# DEGREE_V2.net
KiCad netlist of a schematic drawn in EAGLE
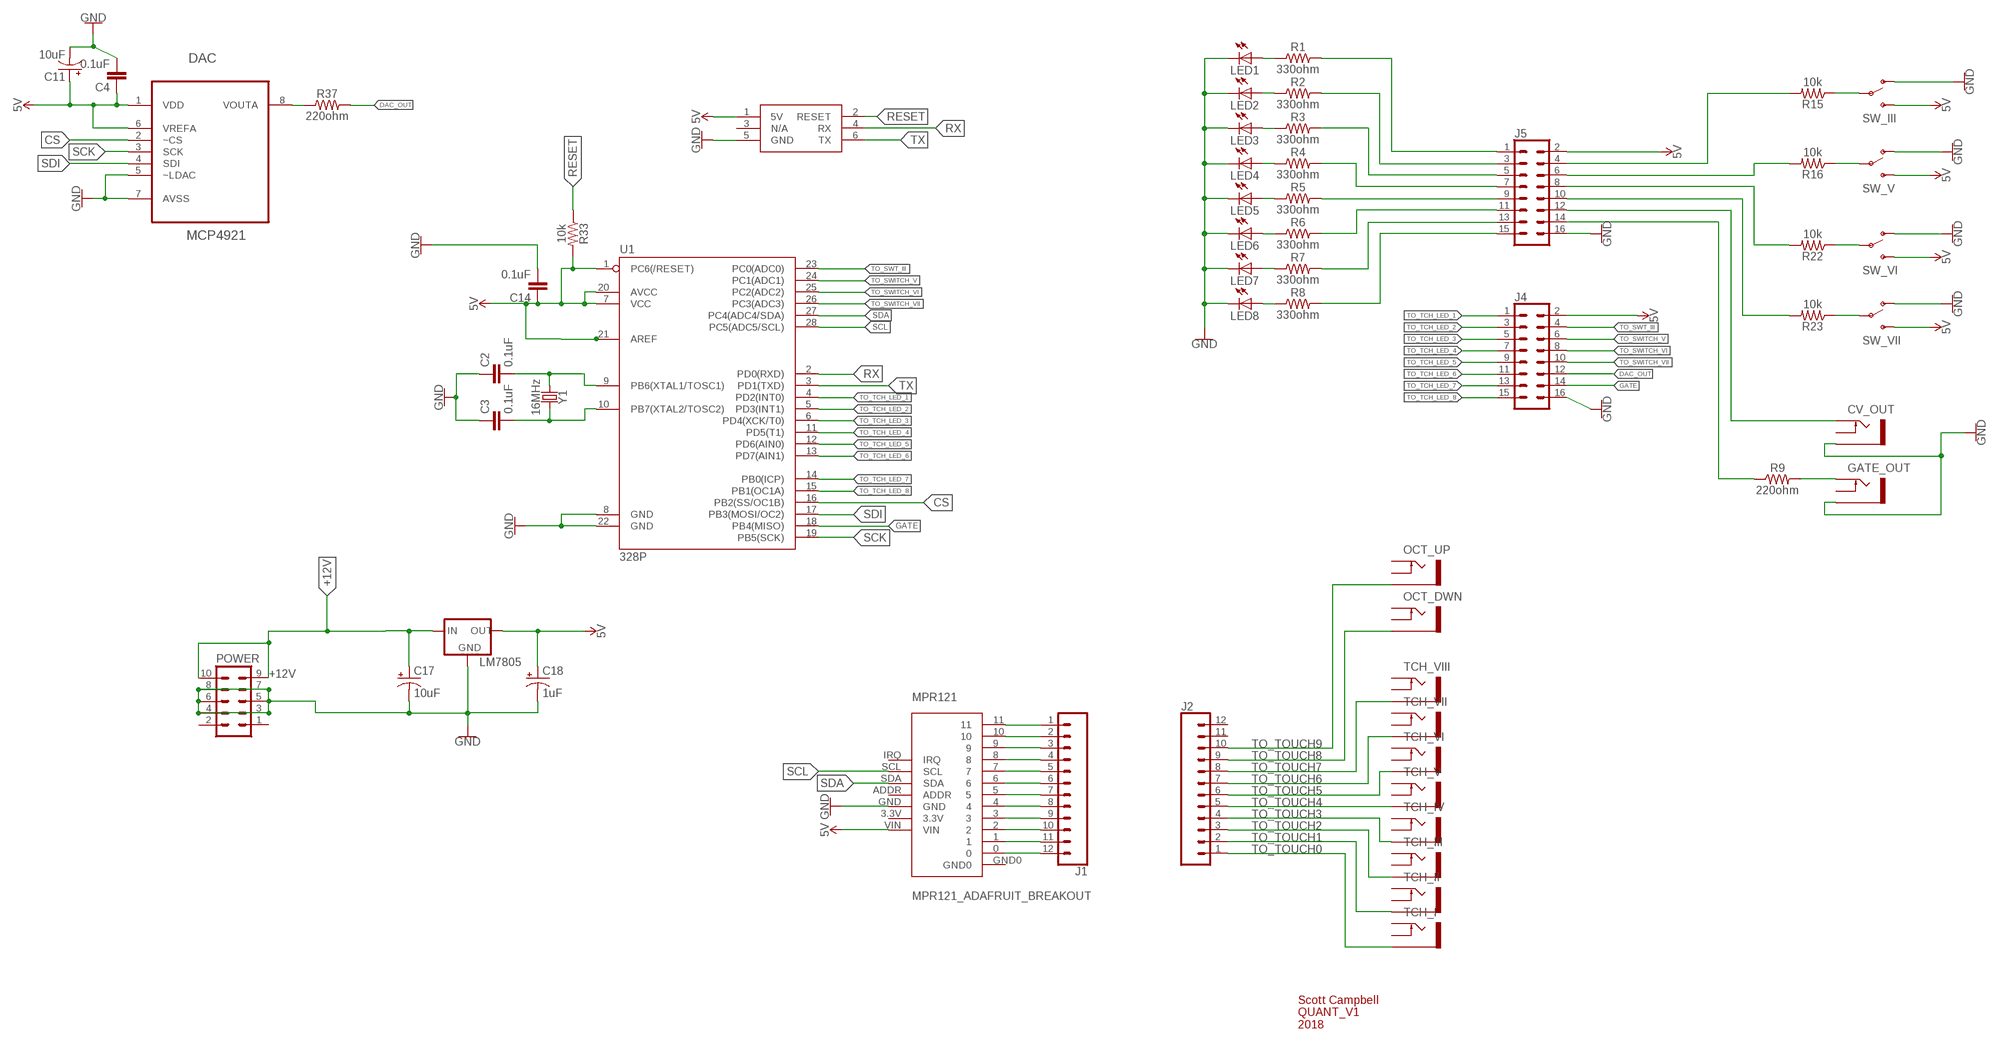
[diagram p0: schematic, sheet 1]

(export (version "E")
  (design (tool "Eeschema 10.0.6"))
  (components
    (comp (ref "C2")
      (value "0.1uF")
      (footprint "eagle-import:CAP-PTH-SMALL-KIT")
      (libsource (lib "eagle-import") (part "0.1UF-KIT-EZ-50V-20%"))
    )
    (comp (ref "C3")
      (value "0.1uF")
      (footprint "eagle-import:CAP-PTH-SMALL-KIT")
      (libsource (lib "eagle-import") (part "0.1UF-KIT-EZ-50V-20%"))
    )
    (comp (ref "C4")
      (value "0.1uF")
      (footprint "eagle-import:CAP-PTH-SMALL-KIT")
      (libsource (lib "eagle-import") (part "0.1UF-KIT-EZ-50V-20%"))
    )
    (comp (ref "C11")
      (value "10uF")
      (footprint "eagle-import:CPOL-RADIAL-2.5MM-5MM")
      (libsource (lib "eagle-import") (part "10UF-POLAR-RADIAL-2.5MM-25V-20%"))
    )
    (comp (ref "C14")
      (value "0.1uF")
      (footprint "eagle-import:CAP-PTH-SMALL-KIT")
      (libsource (lib "eagle-import") (part "0.1UF-KIT-EZ-50V-20%"))
    )
    (comp (ref "C17")
      (value "10uF")
      (footprint "eagle-import:CPOL-RADIAL-2.5MM-5MM")
      (libsource (lib "eagle-import") (part "10UF-POLAR-RADIAL-2.5MM-25V-20%"))
    )
    (comp (ref "C18")
      (value "1uF")
      (footprint "eagle-import:CPOL-RADIAL-2.5MM-5MM")
      (libsource (lib "eagle-import") (part "10UF-POLAR-RADIAL-2.5MM-25V-20%"))
    )
    (comp (ref "CV_OUT")
      (value "CV_OUT")
      (footprint "eagle-import:WQP-PJ301M-12_JACK")
      (libsource (lib "eagle-import") (part "THONKICONNNEW"))
    )
    (comp (ref "DAC")
      (value "MCP4921")
      (footprint "eagle-import:DIP08")
      (libsource (lib "eagle-import") (part "MCP4921"))
    )
    (comp (ref "GATE_OUT")
      (value "GATE_OUT")
      (footprint "eagle-import:WQP-PJ301M-12_JACK")
      (libsource (lib "eagle-import") (part "THONKICONNNEW"))
    )
    (comp (ref "J1")
      (value "CONN_12")
      (footprint "eagle-import:1X12")
      (libsource (lib "eagle-import") (part "CONN_12"))
    )
    (comp (ref "J2")
      (value "CONN_12")
      (footprint "eagle-import:1X12")
      (libsource (lib "eagle-import") (part "CONN_12"))
    )
    (comp (ref "J4")
      (value "CONN_08X2")
      (footprint "eagle-import:2X8")
      (libsource (lib "eagle-import") (part "CONN_08X2"))
    )
    (comp (ref "J5")
      (value "CONN_08X2")
      (footprint "eagle-import:2X8")
      (libsource (lib "eagle-import") (part "CONN_08X2"))
    )
    (comp (ref "LED1")
      (value "LED3MM")
      (footprint "eagle-import:LED3MM")
      (libsource (lib "eagle-import") (part "LED3MM"))
    )
    (comp (ref "LED2")
      (value "LED3MM")
      (footprint "eagle-import:LED3MM")
      (libsource (lib "eagle-import") (part "LED3MM"))
    )
    (comp (ref "LED3")
      (value "LED3MM")
      (footprint "eagle-import:LED3MM")
      (libsource (lib "eagle-import") (part "LED3MM"))
    )
    (comp (ref "LED4")
      (value "LED3MM")
      (footprint "eagle-import:LED3MM")
      (libsource (lib "eagle-import") (part "LED3MM"))
    )
    (comp (ref "LED5")
      (value "LED3MM")
      (footprint "eagle-import:LED3MM")
      (libsource (lib "eagle-import") (part "LED3MM"))
    )
    (comp (ref "LED6")
      (value "LED3MM")
      (footprint "eagle-import:LED3MM")
      (libsource (lib "eagle-import") (part "LED3MM"))
    )
    (comp (ref "LED7")
      (value "LED3MM")
      (footprint "eagle-import:LED3MM")
      (libsource (lib "eagle-import") (part "LED3MM"))
    )
    (comp (ref "LED8")
      (value "LED3MM")
      (footprint "eagle-import:LED3MM")
      (libsource (lib "eagle-import") (part "LED3MM"))
    )
    (comp (ref "LM7805")
      (value "V_REG_78XXTO-92_UNTESTED")
      (footprint "eagle-import:TO-92")
      (libsource (lib "eagle-import") (part "V_REG_78XXTO-92_UNTESTED"))
    )
    (comp (ref "MPR121")
      (value "MPR121_ADAFRUIT_BREAKOUT")
      (footprint "eagle-import:MPR121_ADAFRUIT_BREAKOUT")
      (libsource (lib "eagle-import") (part "MPR121_ADAFRUIT_BREAKOUT"))
    )
    (comp (ref "OCT_DWN")
      (value "THONKICONN-ESSY")
      (footprint "eagle-import:THONKICONN-ESSY")
      (libsource (lib "eagle-import") (part "THONKICONN-ESSY"))
    )
    (comp (ref "OCT_UP")
      (value "THONKICONN-ESSY")
      (footprint "eagle-import:THONKICONN-ESSY")
      (libsource (lib "eagle-import") (part "THONKICONN-ESSY"))
    )
    (comp (ref "POWER")
      (value "EURO_POWER_HEADERREGULAR")
      (footprint "eagle-import:EURO_POWER_HEADER")
      (libsource (lib "eagle-import") (part "EURO_POWER_HEADERREGULAR"))
    )
    (comp (ref "R1")
      (value "330ohm")
      (footprint "eagle-import:AXIAL-0.3")
      (libsource (lib "eagle-import") (part "1KOHM-HORIZ-1/4W-5%"))
    )
    (comp (ref "R2")
      (value "330ohm")
      (footprint "eagle-import:AXIAL-0.3")
      (libsource (lib "eagle-import") (part "1KOHM-HORIZ-1/4W-5%"))
    )
    (comp (ref "R3")
      (value "330ohm")
      (footprint "eagle-import:AXIAL-0.3")
      (libsource (lib "eagle-import") (part "1KOHM-HORIZ-1/4W-5%"))
    )
    (comp (ref "R4")
      (value "330ohm")
      (footprint "eagle-import:AXIAL-0.3")
      (libsource (lib "eagle-import") (part "1KOHM-HORIZ-1/4W-5%"))
    )
    (comp (ref "R5")
      (value "330ohm")
      (footprint "eagle-import:AXIAL-0.3")
      (libsource (lib "eagle-import") (part "1KOHM-HORIZ-1/4W-5%"))
    )
    (comp (ref "R6")
      (value "330ohm")
      (footprint "eagle-import:AXIAL-0.3")
      (libsource (lib "eagle-import") (part "1KOHM-HORIZ-1/4W-5%"))
    )
    (comp (ref "R7")
      (value "330ohm")
      (footprint "eagle-import:AXIAL-0.3")
      (libsource (lib "eagle-import") (part "1KOHM-HORIZ-1/4W-5%"))
    )
    (comp (ref "R8")
      (value "330ohm")
      (footprint "eagle-import:AXIAL-0.3")
      (libsource (lib "eagle-import") (part "1KOHM-HORIZ-1/4W-5%"))
    )
    (comp (ref "R9")
      (value "220ohm")
      (footprint "eagle-import:HORIZONTAL_RESISTOR")
      (libsource (lib "eagle-import") (part "RESISTOR_HORZ"))
    )
    (comp (ref "R15")
      (value "10k")
      (footprint "eagle-import:HORIZONTAL_RESISTOR")
      (libsource (lib "eagle-import") (part "RESISTOR_HORZ"))
    )
    (comp (ref "R16")
      (value "10k")
      (footprint "eagle-import:HORIZONTAL_RESISTOR")
      (libsource (lib "eagle-import") (part "RESISTOR_HORZ"))
    )
    (comp (ref "R22")
      (value "10k")
      (footprint "eagle-import:HORIZONTAL_RESISTOR")
      (libsource (lib "eagle-import") (part "RESISTOR_HORZ"))
    )
    (comp (ref "R23")
      (value "10k")
      (footprint "eagle-import:HORIZONTAL_RESISTOR")
      (libsource (lib "eagle-import") (part "RESISTOR_HORZ"))
    )
    (comp (ref "R33")
      (value "10k")
      (footprint "eagle-import:HORIZONTAL_RESISTOR")
      (libsource (lib "eagle-import") (part "RESISTOR_HORZ"))
    )
    (comp (ref "R37")
      (value "220ohm")
      (footprint "eagle-import:VERTICAL_RESISTOR")
      (libsource (lib "eagle-import") (part "RESISTOR_VERT"))
    )
    (comp (ref "SW_III")
      (value "SUBMINI_SPDT")
      (footprint "eagle-import:SUBMINI_TOGGLE")
      (libsource (lib "eagle-import") (part "SUBMINI_SPDT"))
    )
    (comp (ref "SW_V")
      (value "SUBMINI_SPDT")
      (footprint "eagle-import:SUBMINI_TOGGLE")
      (libsource (lib "eagle-import") (part "SUBMINI_SPDT"))
    )
    (comp (ref "SW_VI")
      (value "SUBMINI_SPDT")
      (footprint "eagle-import:SUBMINI_TOGGLE")
      (libsource (lib "eagle-import") (part "SUBMINI_SPDT"))
    )
    (comp (ref "SW_VII")
      (value "SUBMINI_SPDT")
      (footprint "eagle-import:SUBMINI_TOGGLE")
      (libsource (lib "eagle-import") (part "SUBMINI_SPDT"))
    )
    (comp (ref "TCH_I")
      (value "THONKICONN-ESSY")
      (footprint "eagle-import:THONKICONN-ESSY")
      (libsource (lib "eagle-import") (part "THONKICONN-ESSY"))
    )
    (comp (ref "TCH_II")
      (value "THONKICONN-ESSY")
      (footprint "eagle-import:THONKICONN-ESSY")
      (libsource (lib "eagle-import") (part "THONKICONN-ESSY"))
    )
    (comp (ref "TCH_III")
      (value "THONKICONN-ESSY")
      (footprint "eagle-import:THONKICONN-ESSY")
      (libsource (lib "eagle-import") (part "THONKICONN-ESSY"))
    )
    (comp (ref "TCH_IV")
      (value "THONKICONN-ESSY")
      (footprint "eagle-import:THONKICONN-ESSY")
      (libsource (lib "eagle-import") (part "THONKICONN-ESSY"))
    )
    (comp (ref "TCH_V")
      (value "THONKICONN-ESSY")
      (footprint "eagle-import:THONKICONN-ESSY")
      (libsource (lib "eagle-import") (part "THONKICONN-ESSY"))
    )
    (comp (ref "TCH_VI")
      (value "THONKICONN-ESSY")
      (footprint "eagle-import:THONKICONN-ESSY")
      (libsource (lib "eagle-import") (part "THONKICONN-ESSY"))
    )
    (comp (ref "TCH_VII")
      (value "THONKICONN-ESSY")
      (footprint "eagle-import:THONKICONN-ESSY")
      (libsource (lib "eagle-import") (part "THONKICONN-ESSY"))
    )
    (comp (ref "TCH_VIII")
      (value "THONKICONN-ESSY")
      (footprint "eagle-import:THONKICONN-ESSY")
      (libsource (lib "eagle-import") (part "THONKICONN-ESSY"))
    )
    (comp (ref "U$1")
      (value "ATMEGA_PROGRAMMING_PINS")
      (footprint "eagle-import:ATMEGA_PROGRAMMING_PINS")
      (libsource (lib "eagle-import") (part "ATMEGA_PROGRAMMING_PINS"))
    )
    (comp (ref "U1")
      (value "328P")
      (footprint "eagle-import:DIP28")
      (libsource (lib "eagle-import") (part "ATMEGA328P_PDIP"))
    )
    (comp (ref "Y1")
      (value "16MHz")
      (footprint "eagle-import:HC49US")
      (libsource (lib "eagle-import") (part "CRYSTAL-16MHZPTH-HC49US"))
    )
  )
  (nets
    (net (code "1") (name "+12V") (class "Default")
      (node (ref "C17") (pin "1") (pinfunction "+_1") (pintype "passive"))
      (node (ref "LM7805") (pin "3") (pinfunction "IN_3") (pintype "input"))
      (node (ref "POWER") (pin "10") (pinfunction "10_10") (pintype "passive"))
      (node (ref "POWER") (pin "9") (pinfunction "9_9") (pintype "passive"))
    )
    (net (code "2") (name "/TO_TOUCH0") (class "Default")
      (node (ref "J2") (pin "1") (pinfunction "1_1") (pintype "passive"))
      (node (ref "TCH_I") (pin "P$3_SLEEVE") (pinfunction "SLEEVE_P$3_SLEEVE") (pintype "passive"))
    )
    (net (code "3") (name "/TO_TOUCH1") (class "Default")
      (node (ref "J2") (pin "2") (pinfunction "2_2") (pintype "passive"))
      (node (ref "TCH_II") (pin "P$3_SLEEVE") (pinfunction "SLEEVE_P$3_SLEEVE") (pintype "passive"))
    )
    (net (code "4") (name "/TO_TOUCH2") (class "Default")
      (node (ref "J2") (pin "3") (pinfunction "3_3") (pintype "passive"))
      (node (ref "TCH_III") (pin "P$3_SLEEVE") (pinfunction "SLEEVE_P$3_SLEEVE") (pintype "passive"))
    )
    (net (code "5") (name "/TO_TOUCH3") (class "Default")
      (node (ref "J2") (pin "4") (pinfunction "4_4") (pintype "passive"))
      (node (ref "TCH_IV") (pin "P$3_SLEEVE") (pinfunction "SLEEVE_P$3_SLEEVE") (pintype "passive"))
    )
    (net (code "6") (name "/TO_TOUCH4") (class "Default")
      (node (ref "J2") (pin "5") (pinfunction "5_5") (pintype "passive"))
      (node (ref "TCH_V") (pin "P$3_SLEEVE") (pinfunction "SLEEVE_P$3_SLEEVE") (pintype "passive"))
    )
    (net (code "7") (name "/TO_TOUCH5") (class "Default")
      (node (ref "J2") (pin "6") (pinfunction "6_6") (pintype "passive"))
      (node (ref "TCH_VI") (pin "P$3_SLEEVE") (pinfunction "SLEEVE_P$3_SLEEVE") (pintype "passive"))
    )
    (net (code "8") (name "/TO_TOUCH6") (class "Default")
      (node (ref "J2") (pin "7") (pinfunction "7_7") (pintype "passive"))
      (node (ref "TCH_VII") (pin "P$3_SLEEVE") (pinfunction "SLEEVE_P$3_SLEEVE") (pintype "passive"))
    )
    (net (code "9") (name "/TO_TOUCH7") (class "Default")
      (node (ref "J2") (pin "8") (pinfunction "8_8") (pintype "passive"))
      (node (ref "TCH_VIII") (pin "P$3_SLEEVE") (pinfunction "SLEEVE_P$3_SLEEVE") (pintype "passive"))
    )
    (net (code "10") (name "/TO_TOUCH8") (class "Default")
      (node (ref "J2") (pin "9") (pinfunction "9_9") (pintype "passive"))
      (node (ref "OCT_DWN") (pin "P$3_SLEEVE") (pinfunction "SLEEVE_P$3_SLEEVE") (pintype "passive"))
    )
    (net (code "11") (name "/TO_TOUCH9") (class "Default")
      (node (ref "J2") (pin "10") (pinfunction "10_10") (pintype "passive"))
      (node (ref "OCT_UP") (pin "P$3_SLEEVE") (pinfunction "SLEEVE_P$3_SLEEVE") (pintype "passive"))
    )
    (net (code "12") (name "5V") (class "Default")
      (node (ref "C11") (pin "1") (pinfunction "+_1") (pintype "passive"))
      (node (ref "C14") (pin "1") (pinfunction "1_1") (pintype "passive"))
      (node (ref "C18") (pin "1") (pinfunction "+_1") (pintype "passive"))
      (node (ref "C4") (pin "1") (pinfunction "1_1") (pintype "passive"))
      (node (ref "DAC") (pin "1") (pinfunction "VDD_1") (pintype "power_in"))
      (node (ref "DAC") (pin "6") (pinfunction "VREFA_6") (pintype "input"))
      (node (ref "J4") (pin "2") (pinfunction "2_2") (pintype "passive"))
      (node (ref "J5") (pin "2") (pinfunction "2_2") (pintype "passive"))
      (node (ref "LM7805") (pin "1") (pinfunction "OUT_1") (pintype "passive"))
      (node (ref "MPR121") (pin "VIN") (pinfunction "VIN_VIN") (pintype "bidirectional"))
      (node (ref "R33") (pin "2") (pinfunction "2_2") (pintype "passive"))
      (node (ref "SW_III") (pin "3") (pinfunction "S_3") (pintype "passive"))
      (node (ref "SW_V") (pin "3") (pinfunction "S_3") (pintype "passive"))
      (node (ref "SW_VI") (pin "3") (pinfunction "S_3") (pintype "passive"))
      (node (ref "SW_VII") (pin "3") (pinfunction "S_3") (pintype "passive"))
      (node (ref "U$1") (pin "1") (pinfunction "5V_1") (pintype "bidirectional"))
      (node (ref "U1") (pin "1") (pinfunction "PC6(/RESET)_1") (pintype "bidirectional"))
      (node (ref "U1") (pin "20") (pinfunction "AVCC_20") (pintype "bidirectional"))
      (node (ref "U1") (pin "21") (pinfunction "AREF_21") (pintype "bidirectional"))
      (node (ref "U1") (pin "7") (pinfunction "VCC_7") (pintype "bidirectional"))
    )
    (net (code "13") (name "CS") (class "Default")
      (node (ref "DAC") (pin "2") (pinfunction "~{CS}_2") (pintype "input"))
      (node (ref "U1") (pin "16") (pinfunction "PB2(SS/OC1B)_16") (pintype "bidirectional"))
    )
    (net (code "14") (name "DAC_OUT") (class "Default")
      (node (ref "J4") (pin "12") (pinfunction "12_12") (pintype "passive"))
      (node (ref "R37") (pin "2") (pinfunction "2_2") (pintype "passive"))
    )
    (net (code "15") (name "GATE") (class "Default")
      (node (ref "J4") (pin "14") (pinfunction "14_14") (pintype "passive"))
      (node (ref "U1") (pin "18") (pinfunction "PB4(MISO)_18") (pintype "bidirectional"))
    )
    (net (code "16") (name "GND") (class "Default")
      (node (ref "C11") (pin "2") (pinfunction "-_2") (pintype "passive"))
      (node (ref "C14") (pin "2") (pinfunction "2_2") (pintype "passive"))
      (node (ref "C17") (pin "2") (pinfunction "-_2") (pintype "passive"))
      (node (ref "C18") (pin "2") (pinfunction "-_2") (pintype "passive"))
      (node (ref "C2") (pin "1") (pinfunction "1_1") (pintype "passive"))
      (node (ref "C3") (pin "1") (pinfunction "1_1") (pintype "passive"))
      (node (ref "C4") (pin "2") (pinfunction "2_2") (pintype "passive"))
      (node (ref "CV_OUT") (pin "P$3_SLEEVE") (pinfunction "SLEEVE_P$3_SLEEVE") (pintype "passive"))
      (node (ref "DAC") (pin "5") (pinfunction "~{LDAC}_5") (pintype "input"))
      (node (ref "DAC") (pin "7") (pinfunction "AVSS_7") (pintype "passive"))
      (node (ref "GATE_OUT") (pin "P$3_SLEEVE") (pinfunction "SLEEVE_P$3_SLEEVE") (pintype "passive"))
      (node (ref "J4") (pin "16") (pinfunction "16_16") (pintype "passive"))
      (node (ref "J5") (pin "16") (pinfunction "16_16") (pintype "passive"))
      (node (ref "LED1") (pin "K") (pinfunction "C_K") (pintype "passive"))
      (node (ref "LED2") (pin "K") (pinfunction "C_K") (pintype "passive"))
      (node (ref "LED3") (pin "K") (pinfunction "C_K") (pintype "passive"))
      (node (ref "LED4") (pin "K") (pinfunction "C_K") (pintype "passive"))
      (node (ref "LED5") (pin "K") (pinfunction "C_K") (pintype "passive"))
      (node (ref "LED6") (pin "K") (pinfunction "C_K") (pintype "passive"))
      (node (ref "LED7") (pin "K") (pinfunction "C_K") (pintype "passive"))
      (node (ref "LED8") (pin "K") (pinfunction "C_K") (pintype "passive"))
      (node (ref "LM7805") (pin "2") (pinfunction "GND_2") (pintype "input"))
      (node (ref "MPR121") (pin "GND") (pinfunction "GND_GND") (pintype "bidirectional"))
      (node (ref "POWER") (pin "3") (pinfunction "3_3") (pintype "passive"))
      (node (ref "POWER") (pin "4") (pinfunction "4_4") (pintype "passive"))
      (node (ref "POWER") (pin "5") (pinfunction "5_5") (pintype "passive"))
      (node (ref "POWER") (pin "6") (pinfunction "6_6") (pintype "passive"))
      (node (ref "POWER") (pin "7") (pinfunction "7_7") (pintype "passive"))
      (node (ref "POWER") (pin "8") (pinfunction "8_8") (pintype "passive"))
      (node (ref "SW_III") (pin "1") (pinfunction "O_1") (pintype "passive"))
      (node (ref "SW_V") (pin "1") (pinfunction "O_1") (pintype "passive"))
      (node (ref "SW_VI") (pin "1") (pinfunction "O_1") (pintype "passive"))
      (node (ref "SW_VII") (pin "1") (pinfunction "O_1") (pintype "passive"))
      (node (ref "U$1") (pin "5") (pinfunction "GND_5") (pintype "bidirectional"))
      (node (ref "U1") (pin "22") (pinfunction "GND_22") (pintype "bidirectional"))
      (node (ref "U1") (pin "8") (pinfunction "GND_8") (pintype "bidirectional"))
    )
    (net (code "17") (name "Net-(CV_OUT-TIP)") (class "Default")
      (node (ref "CV_OUT") (pin "P$1_TIP") (pinfunction "TIP_P$1_TIP") (pintype "passive"))
      (node (ref "J5") (pin "12") (pinfunction "12_12") (pintype "passive"))
    )
    (net (code "18") (name "Net-(DAC-VOUTA)") (class "Default")
      (node (ref "DAC") (pin "8") (pinfunction "VOUTA_8") (pintype "output"))
      (node (ref "R37") (pin "1") (pinfunction "1_1") (pintype "passive"))
    )
    (net (code "19") (name "Net-(GATE_OUT-TIP)") (class "Default")
      (node (ref "GATE_OUT") (pin "P$1_TIP") (pinfunction "TIP_P$1_TIP") (pintype "passive"))
      (node (ref "R9") (pin "2") (pinfunction "2_2") (pintype "passive"))
    )
    (net (code "20") (name "Net-(J1-Pad1)") (class "Default")
      (node (ref "J1") (pin "1") (pinfunction "1_1") (pintype "passive"))
      (node (ref "MPR121") (pin "11") (pinfunction "11_11") (pintype "bidirectional"))
    )
    (net (code "21") (name "Net-(J1-Pad2)") (class "Default")
      (node (ref "J1") (pin "2") (pinfunction "2_2") (pintype "passive"))
      (node (ref "MPR121") (pin "10") (pinfunction "10_10") (pintype "bidirectional"))
    )
    (net (code "22") (name "Net-(J1-Pad3)") (class "Default")
      (node (ref "J1") (pin "3") (pinfunction "3_3") (pintype "passive"))
      (node (ref "MPR121") (pin "9") (pinfunction "9_9") (pintype "bidirectional"))
    )
    (net (code "23") (name "Net-(J1-Pad4)") (class "Default")
      (node (ref "J1") (pin "4") (pinfunction "4_4") (pintype "passive"))
      (node (ref "MPR121") (pin "8") (pinfunction "8_8") (pintype "bidirectional"))
    )
    (net (code "24") (name "Net-(J1-Pad5)") (class "Default")
      (node (ref "J1") (pin "5") (pinfunction "5_5") (pintype "passive"))
      (node (ref "MPR121") (pin "7") (pinfunction "7_7") (pintype "bidirectional"))
    )
    (net (code "25") (name "Net-(J1-Pad6)") (class "Default")
      (node (ref "J1") (pin "6") (pinfunction "6_6") (pintype "passive"))
      (node (ref "MPR121") (pin "6") (pinfunction "6_6") (pintype "bidirectional"))
    )
    (net (code "26") (name "Net-(J1-Pad7)") (class "Default")
      (node (ref "J1") (pin "7") (pinfunction "7_7") (pintype "passive"))
      (node (ref "MPR121") (pin "5") (pinfunction "5_5") (pintype "bidirectional"))
    )
    (net (code "27") (name "Net-(J1-Pad8)") (class "Default")
      (node (ref "J1") (pin "8") (pinfunction "8_8") (pintype "passive"))
      (node (ref "MPR121") (pin "4") (pinfunction "4_4") (pintype "bidirectional"))
    )
    (net (code "28") (name "Net-(J1-Pad9)") (class "Default")
      (node (ref "J1") (pin "9") (pinfunction "9_9") (pintype "passive"))
      (node (ref "MPR121") (pin "3") (pinfunction "3_3") (pintype "bidirectional"))
    )
    (net (code "29") (name "Net-(J1-Pad10)") (class "Default")
      (node (ref "J1") (pin "10") (pinfunction "10_10") (pintype "passive"))
      (node (ref "MPR121") (pin "2") (pinfunction "2_2") (pintype "bidirectional"))
    )
    (net (code "30") (name "Net-(J1-Pad11)") (class "Default")
      (node (ref "J1") (pin "11") (pinfunction "11_11") (pintype "passive"))
      (node (ref "MPR121") (pin "1") (pinfunction "1_1") (pintype "bidirectional"))
    )
    (net (code "31") (name "Net-(J1-Pad12)") (class "Default")
      (node (ref "J1") (pin "12") (pinfunction "12_12") (pintype "passive"))
      (node (ref "MPR121") (pin "0") (pinfunction "0_0") (pintype "bidirectional"))
    )
    (net (code "32") (name "Net-(J5-Pad4)") (class "Default")
      (node (ref "J5") (pin "4") (pinfunction "4_4") (pintype "passive"))
      (node (ref "R15") (pin "2") (pinfunction "2_2") (pintype "passive"))
    )
    (net (code "33") (name "Net-(J5-Pad6)") (class "Default")
      (node (ref "J5") (pin "6") (pinfunction "6_6") (pintype "passive"))
      (node (ref "R16") (pin "2") (pinfunction "2_2") (pintype "passive"))
    )
    (net (code "34") (name "Net-(J5-Pad8)") (class "Default")
      (node (ref "J5") (pin "8") (pinfunction "8_8") (pintype "passive"))
      (node (ref "R22") (pin "2") (pinfunction "2_2") (pintype "passive"))
    )
    (net (code "35") (name "Net-(J5-Pad10)") (class "Default")
      (node (ref "J5") (pin "10") (pinfunction "10_10") (pintype "passive"))
      (node (ref "R23") (pin "2") (pinfunction "2_2") (pintype "passive"))
    )
    (net (code "36") (name "Net-(J5-Pad14)") (class "Default")
      (node (ref "J5") (pin "14") (pinfunction "14_14") (pintype "passive"))
      (node (ref "R9") (pin "1") (pinfunction "1_1") (pintype "passive"))
    )
    (net (code "37") (name "Net-(R1-1)") (class "Default")
      (node (ref "LED1") (pin "A") (pinfunction "A_A") (pintype "passive"))
      (node (ref "R1") (pin "P$1") (pinfunction "1_P$1") (pintype "passive"))
    )
    (net (code "38") (name "Net-(R1-2)") (class "Default")
      (node (ref "J5") (pin "1") (pinfunction "1_1") (pintype "passive"))
      (node (ref "R1") (pin "P$2") (pinfunction "2_P$2") (pintype "passive"))
    )
    (net (code "39") (name "Net-(R2-1)") (class "Default")
      (node (ref "LED2") (pin "A") (pinfunction "A_A") (pintype "passive"))
      (node (ref "R2") (pin "P$1") (pinfunction "1_P$1") (pintype "passive"))
    )
    (net (code "40") (name "Net-(R2-2)") (class "Default")
      (node (ref "J5") (pin "3") (pinfunction "3_3") (pintype "passive"))
      (node (ref "R2") (pin "P$2") (pinfunction "2_P$2") (pintype "passive"))
    )
    (net (code "41") (name "Net-(R3-1)") (class "Default")
      (node (ref "LED3") (pin "A") (pinfunction "A_A") (pintype "passive"))
      (node (ref "R3") (pin "P$1") (pinfunction "1_P$1") (pintype "passive"))
    )
    (net (code "42") (name "Net-(R3-2)") (class "Default")
      (node (ref "J5") (pin "5") (pinfunction "5_5") (pintype "passive"))
      (node (ref "R3") (pin "P$2") (pinfunction "2_P$2") (pintype "passive"))
    )
    (net (code "43") (name "Net-(R4-1)") (class "Default")
      (node (ref "LED4") (pin "A") (pinfunction "A_A") (pintype "passive"))
      (node (ref "R4") (pin "P$1") (pinfunction "1_P$1") (pintype "passive"))
    )
    (net (code "44") (name "Net-(R4-2)") (class "Default")
      (node (ref "J5") (pin "7") (pinfunction "7_7") (pintype "passive"))
      (node (ref "R4") (pin "P$2") (pinfunction "2_P$2") (pintype "passive"))
    )
    (net (code "45") (name "Net-(R5-1)") (class "Default")
      (node (ref "LED5") (pin "A") (pinfunction "A_A") (pintype "passive"))
      (node (ref "R5") (pin "P$1") (pinfunction "1_P$1") (pintype "passive"))
    )
    (net (code "46") (name "Net-(R5-2)") (class "Default")
      (node (ref "J5") (pin "9") (pinfunction "9_9") (pintype "passive"))
      (node (ref "R5") (pin "P$2") (pinfunction "2_P$2") (pintype "passive"))
    )
    (net (code "47") (name "Net-(R6-1)") (class "Default")
      (node (ref "LED6") (pin "A") (pinfunction "A_A") (pintype "passive"))
      (node (ref "R6") (pin "P$1") (pinfunction "1_P$1") (pintype "passive"))
    )
    (net (code "48") (name "Net-(R6-2)") (class "Default")
      (node (ref "J5") (pin "11") (pinfunction "11_11") (pintype "passive"))
      (node (ref "R6") (pin "P$2") (pinfunction "2_P$2") (pintype "passive"))
    )
    (net (code "49") (name "Net-(R7-1)") (class "Default")
      (node (ref "LED7") (pin "A") (pinfunction "A_A") (pintype "passive"))
      (node (ref "R7") (pin "P$1") (pinfunction "1_P$1") (pintype "passive"))
    )
    (net (code "50") (name "Net-(R7-2)") (class "Default")
      (node (ref "J5") (pin "13") (pinfunction "13_13") (pintype "passive"))
      (node (ref "R7") (pin "P$2") (pinfunction "2_P$2") (pintype "passive"))
    )
    (net (code "51") (name "Net-(R8-1)") (class "Default")
      (node (ref "LED8") (pin "A") (pinfunction "A_A") (pintype "passive"))
      (node (ref "R8") (pin "P$1") (pinfunction "1_P$1") (pintype "passive"))
    )
    (net (code "52") (name "Net-(R8-2)") (class "Default")
      (node (ref "J5") (pin "15") (pinfunction "15_15") (pintype "passive"))
      (node (ref "R8") (pin "P$2") (pinfunction "2_P$2") (pintype "passive"))
    )
    (net (code "53") (name "Net-(SW_III-COMMON)") (class "Default")
      (node (ref "R15") (pin "1") (pinfunction "1_1") (pintype "passive"))
      (node (ref "SW_III") (pin "COM") (pinfunction "COMMON_COM") (pintype "passive"))
    )
    (net (code "54") (name "Net-(SW_V-COMMON)") (class "Default")
      (node (ref "R16") (pin "1") (pinfunction "1_1") (pintype "passive"))
      (node (ref "SW_V") (pin "COM") (pinfunction "COMMON_COM") (pintype "passive"))
    )
    (net (code "55") (name "Net-(SW_VI-COMMON)") (class "Default")
      (node (ref "R22") (pin "1") (pinfunction "1_1") (pintype "passive"))
      (node (ref "SW_VI") (pin "COM") (pinfunction "COMMON_COM") (pintype "passive"))
    )
    (net (code "56") (name "Net-(SW_VII-COMMON)") (class "Default")
      (node (ref "R23") (pin "1") (pinfunction "1_1") (pintype "passive"))
      (node (ref "SW_VII") (pin "COM") (pinfunction "COMMON_COM") (pintype "passive"))
    )
    (net (code "57") (name "Net-(U1-PB6(XTAL1{slash}TOSC1))") (class "Default")
      (node (ref "C2") (pin "2") (pinfunction "2_2") (pintype "passive"))
      (node (ref "U1") (pin "9") (pinfunction "PB6(XTAL1/TOSC1)_9") (pintype "bidirectional"))
      (node (ref "Y1") (pin "1") (pinfunction "1_1") (pintype "passive"))
    )
    (net (code "58") (name "Net-(U1-PB7(XTAL2{slash}TOSC2))") (class "Default")
      (node (ref "C3") (pin "2") (pinfunction "2_2") (pintype "passive"))
      (node (ref "U1") (pin "10") (pinfunction "PB7(XTAL2/TOSC2)_10") (pintype "bidirectional"))
      (node (ref "Y1") (pin "2") (pinfunction "2_2") (pintype "passive"))
    )
    (net (code "59") (name "RESET") (class "Default")
      (node (ref "R33") (pin "1") (pinfunction "1_1") (pintype "passive"))
      (node (ref "U$1") (pin "2") (pinfunction "RESET_2") (pintype "bidirectional"))
    )
    (net (code "60") (name "RX") (class "Default")
      (node (ref "U$1") (pin "4") (pinfunction "RX_4") (pintype "bidirectional"))
      (node (ref "U1") (pin "2") (pinfunction "PD0(RXD)_2") (pintype "bidirectional"))
    )
    (net (code "61") (name "SCK") (class "Default")
      (node (ref "DAC") (pin "3") (pinfunction "SCK_3") (pintype "input"))
      (node (ref "U1") (pin "19") (pinfunction "PB5(SCK)_19") (pintype "bidirectional"))
    )
    (net (code "62") (name "SCL") (class "Default")
      (node (ref "MPR121") (pin "SCL") (pinfunction "SCL_SCL") (pintype "bidirectional"))
      (node (ref "U1") (pin "28") (pinfunction "PC5(ADC5/SCL)_28") (pintype "bidirectional"))
    )
    (net (code "63") (name "SDA") (class "Default")
      (node (ref "MPR121") (pin "SDA") (pinfunction "SDA_SDA") (pintype "bidirectional"))
      (node (ref "U1") (pin "27") (pinfunction "PC4(ADC4/SDA)_27") (pintype "bidirectional"))
    )
    (net (code "64") (name "SDI") (class "Default")
      (node (ref "DAC") (pin "4") (pinfunction "SDI_4") (pintype "input"))
      (node (ref "U1") (pin "17") (pinfunction "PB3(MOSI/OC2)_17") (pintype "bidirectional"))
    )
    (net (code "65") (name "TO_SWITCH_V") (class "Default")
      (node (ref "J4") (pin "6") (pinfunction "6_6") (pintype "passive"))
      (node (ref "U1") (pin "24") (pinfunction "PC1(ADC1)_24") (pintype "bidirectional"))
    )
    (net (code "66") (name "TO_SWITCH_VI") (class "Default")
      (node (ref "J4") (pin "8") (pinfunction "8_8") (pintype "passive"))
      (node (ref "U1") (pin "25") (pinfunction "PC2(ADC2)_25") (pintype "bidirectional"))
    )
    (net (code "67") (name "TO_SWITCH_VII") (class "Default")
      (node (ref "J4") (pin "10") (pinfunction "10_10") (pintype "passive"))
      (node (ref "U1") (pin "26") (pinfunction "PC3(ADC3)_26") (pintype "bidirectional"))
    )
    (net (code "68") (name "TO_SWT_III") (class "Default")
      (node (ref "J4") (pin "4") (pinfunction "4_4") (pintype "passive"))
      (node (ref "U1") (pin "23") (pinfunction "PC0(ADC0)_23") (pintype "bidirectional"))
    )
    (net (code "69") (name "TO_TCH_LED_1") (class "Default")
      (node (ref "J4") (pin "1") (pinfunction "1_1") (pintype "passive"))
      (node (ref "U1") (pin "4") (pinfunction "PD2(INT0)_4") (pintype "bidirectional"))
    )
    (net (code "70") (name "TO_TCH_LED_2") (class "Default")
      (node (ref "J4") (pin "3") (pinfunction "3_3") (pintype "passive"))
      (node (ref "U1") (pin "5") (pinfunction "PD3(INT1)_5") (pintype "bidirectional"))
    )
    (net (code "71") (name "TO_TCH_LED_3") (class "Default")
      (node (ref "J4") (pin "5") (pinfunction "5_5") (pintype "passive"))
      (node (ref "U1") (pin "6") (pinfunction "PD4(XCK/T0)_6") (pintype "bidirectional"))
    )
    (net (code "72") (name "TO_TCH_LED_4") (class "Default")
      (node (ref "J4") (pin "7") (pinfunction "7_7") (pintype "passive"))
      (node (ref "U1") (pin "11") (pinfunction "PD5(T1)_11") (pintype "bidirectional"))
    )
    (net (code "73") (name "TO_TCH_LED_5") (class "Default")
      (node (ref "J4") (pin "9") (pinfunction "9_9") (pintype "passive"))
      (node (ref "U1") (pin "12") (pinfunction "PD6(AIN0)_12") (pintype "bidirectional"))
    )
    (net (code "74") (name "TO_TCH_LED_6") (class "Default")
      (node (ref "J4") (pin "11") (pinfunction "11_11") (pintype "passive"))
      (node (ref "U1") (pin "13") (pinfunction "PD7(AIN1)_13") (pintype "bidirectional"))
    )
    (net (code "75") (name "TO_TCH_LED_7") (class "Default")
      (node (ref "J4") (pin "13") (pinfunction "13_13") (pintype "passive"))
      (node (ref "U1") (pin "14") (pinfunction "PB0(ICP)_14") (pintype "bidirectional"))
    )
    (net (code "76") (name "TO_TCH_LED_8") (class "Default")
      (node (ref "J4") (pin "15") (pinfunction "15_15") (pintype "passive"))
      (node (ref "U1") (pin "15") (pinfunction "PB1(OC1A)_15") (pintype "bidirectional"))
    )
    (net (code "77") (name "TX") (class "Default")
      (node (ref "U$1") (pin "6") (pinfunction "TX_6") (pintype "bidirectional"))
      (node (ref "U1") (pin "3") (pinfunction "PD1(TXD)_3") (pintype "bidirectional"))
    )
    (net (code "78") (name "unconnected-(CV_OUT-SWITCH-PadP$2_SWITCH)") (class "Default")
      (node (ref "CV_OUT") (pin "P$2_SWITCH") (pinfunction "SWITCH_P$2_SWITCH") (pintype "passive"))
    )
    (net (code "79") (name "unconnected-(GATE_OUT-SWITCH-PadP$2_SWITCH)") (class "Default")
      (node (ref "GATE_OUT") (pin "P$2_SWITCH") (pinfunction "SWITCH_P$2_SWITCH") (pintype "passive"))
    )
    (net (code "80") (name "unconnected-(J2-Pad11)") (class "Default")
      (node (ref "J2") (pin "11") (pinfunction "11_11") (pintype "passive"))
    )
    (net (code "81") (name "unconnected-(J2-Pad12)") (class "Default")
      (node (ref "J2") (pin "12") (pinfunction "12_12") (pintype "passive"))
    )
    (net (code "82") (name "unconnected-(MPR121-Pad3.3V)") (class "Default")
      (node (ref "MPR121") (pin "3.3V") (pinfunction "3.3V_3.3V") (pintype "bidirectional"))
    )
    (net (code "83") (name "unconnected-(MPR121-PadADDR)") (class "Default")
      (node (ref "MPR121") (pin "ADDR") (pinfunction "ADDR_ADDR") (pintype "bidirectional"))
    )
    (net (code "84") (name "unconnected-(MPR121-PadGND0)") (class "Default")
      (node (ref "MPR121") (pin "GND0") (pinfunction "GND0_GND0") (pintype "bidirectional"))
    )
    (net (code "85") (name "unconnected-(MPR121-PadIRQ)") (class "Default")
      (node (ref "MPR121") (pin "IRQ") (pinfunction "IRQ_IRQ") (pintype "bidirectional"))
    )
    (net (code "86") (name "unconnected-(OCT_DWN-SWITCH-PadP$2_SWITCH)") (class "Default")
      (node (ref "OCT_DWN") (pin "P$2_SWITCH") (pinfunction "SWITCH_P$2_SWITCH") (pintype "passive"))
    )
    (net (code "87") (name "unconnected-(OCT_DWN-TIP-PadP$1_TIP)") (class "Default")
      (node (ref "OCT_DWN") (pin "P$1_TIP") (pinfunction "TIP_P$1_TIP") (pintype "passive"))
    )
    (net (code "88") (name "unconnected-(OCT_UP-SWITCH-PadP$2_SWITCH)") (class "Default")
      (node (ref "OCT_UP") (pin "P$2_SWITCH") (pinfunction "SWITCH_P$2_SWITCH") (pintype "passive"))
    )
    (net (code "89") (name "unconnected-(OCT_UP-TIP-PadP$1_TIP)") (class "Default")
      (node (ref "OCT_UP") (pin "P$1_TIP") (pinfunction "TIP_P$1_TIP") (pintype "passive"))
    )
    (net (code "90") (name "unconnected-(POWER-Pad1)") (class "Default")
      (node (ref "POWER") (pin "1") (pinfunction "1_1") (pintype "passive"))
    )
    (net (code "91") (name "unconnected-(POWER-Pad2)") (class "Default")
      (node (ref "POWER") (pin "2") (pinfunction "2_2") (pintype "passive"))
    )
    (net (code "92") (name "unconnected-(TCH_I-SWITCH-PadP$2_SWITCH)") (class "Default")
      (node (ref "TCH_I") (pin "P$2_SWITCH") (pinfunction "SWITCH_P$2_SWITCH") (pintype "passive"))
    )
    (net (code "93") (name "unconnected-(TCH_I-TIP-PadP$1_TIP)") (class "Default")
      (node (ref "TCH_I") (pin "P$1_TIP") (pinfunction "TIP_P$1_TIP") (pintype "passive"))
    )
    (net (code "94") (name "unconnected-(TCH_II-SWITCH-PadP$2_SWITCH)") (class "Default")
      (node (ref "TCH_II") (pin "P$2_SWITCH") (pinfunction "SWITCH_P$2_SWITCH") (pintype "passive"))
    )
    (net (code "95") (name "unconnected-(TCH_II-TIP-PadP$1_TIP)") (class "Default")
      (node (ref "TCH_II") (pin "P$1_TIP") (pinfunction "TIP_P$1_TIP") (pintype "passive"))
    )
    (net (code "96") (name "unconnected-(TCH_III-SWITCH-PadP$2_SWITCH)") (class "Default")
      (node (ref "TCH_III") (pin "P$2_SWITCH") (pinfunction "SWITCH_P$2_SWITCH") (pintype "passive"))
    )
    (net (code "97") (name "unconnected-(TCH_III-TIP-PadP$1_TIP)") (class "Default")
      (node (ref "TCH_III") (pin "P$1_TIP") (pinfunction "TIP_P$1_TIP") (pintype "passive"))
    )
    (net (code "98") (name "unconnected-(TCH_IV-SWITCH-PadP$2_SWITCH)") (class "Default")
      (node (ref "TCH_IV") (pin "P$2_SWITCH") (pinfunction "SWITCH_P$2_SWITCH") (pintype "passive"))
    )
    (net (code "99") (name "unconnected-(TCH_IV-TIP-PadP$1_TIP)") (class "Default")
      (node (ref "TCH_IV") (pin "P$1_TIP") (pinfunction "TIP_P$1_TIP") (pintype "passive"))
    )
    (net (code "100") (name "unconnected-(TCH_V-SWITCH-PadP$2_SWITCH)") (class "Default")
      (node (ref "TCH_V") (pin "P$2_SWITCH") (pinfunction "SWITCH_P$2_SWITCH") (pintype "passive"))
    )
    (net (code "101") (name "unconnected-(TCH_V-TIP-PadP$1_TIP)") (class "Default")
      (node (ref "TCH_V") (pin "P$1_TIP") (pinfunction "TIP_P$1_TIP") (pintype "passive"))
    )
    (net (code "102") (name "unconnected-(TCH_VI-SWITCH-PadP$2_SWITCH)") (class "Default")
      (node (ref "TCH_VI") (pin "P$2_SWITCH") (pinfunction "SWITCH_P$2_SWITCH") (pintype "passive"))
    )
    (net (code "103") (name "unconnected-(TCH_VI-TIP-PadP$1_TIP)") (class "Default")
      (node (ref "TCH_VI") (pin "P$1_TIP") (pinfunction "TIP_P$1_TIP") (pintype "passive"))
    )
    (net (code "104") (name "unconnected-(TCH_VII-SWITCH-PadP$2_SWITCH)") (class "Default")
      (node (ref "TCH_VII") (pin "P$2_SWITCH") (pinfunction "SWITCH_P$2_SWITCH") (pintype "passive"))
    )
    (net (code "105") (name "unconnected-(TCH_VII-TIP-PadP$1_TIP)") (class "Default")
      (node (ref "TCH_VII") (pin "P$1_TIP") (pinfunction "TIP_P$1_TIP") (pintype "passive"))
    )
    (net (code "106") (name "unconnected-(TCH_VIII-SWITCH-PadP$2_SWITCH)") (class "Default")
      (node (ref "TCH_VIII") (pin "P$2_SWITCH") (pinfunction "SWITCH_P$2_SWITCH") (pintype "passive"))
    )
    (net (code "107") (name "unconnected-(TCH_VIII-TIP-PadP$1_TIP)") (class "Default")
      (node (ref "TCH_VIII") (pin "P$1_TIP") (pinfunction "TIP_P$1_TIP") (pintype "passive"))
    )
    (net (code "108") (name "unconnected-(U$1-N{slash}A-Pad3)") (class "Default")
      (node (ref "U$1") (pin "3") (pinfunction "N/A_3") (pintype "bidirectional"))
    )
  )
)
